# circuitMain.net
KiCad netlist of a schematic drawn in Altium Designer
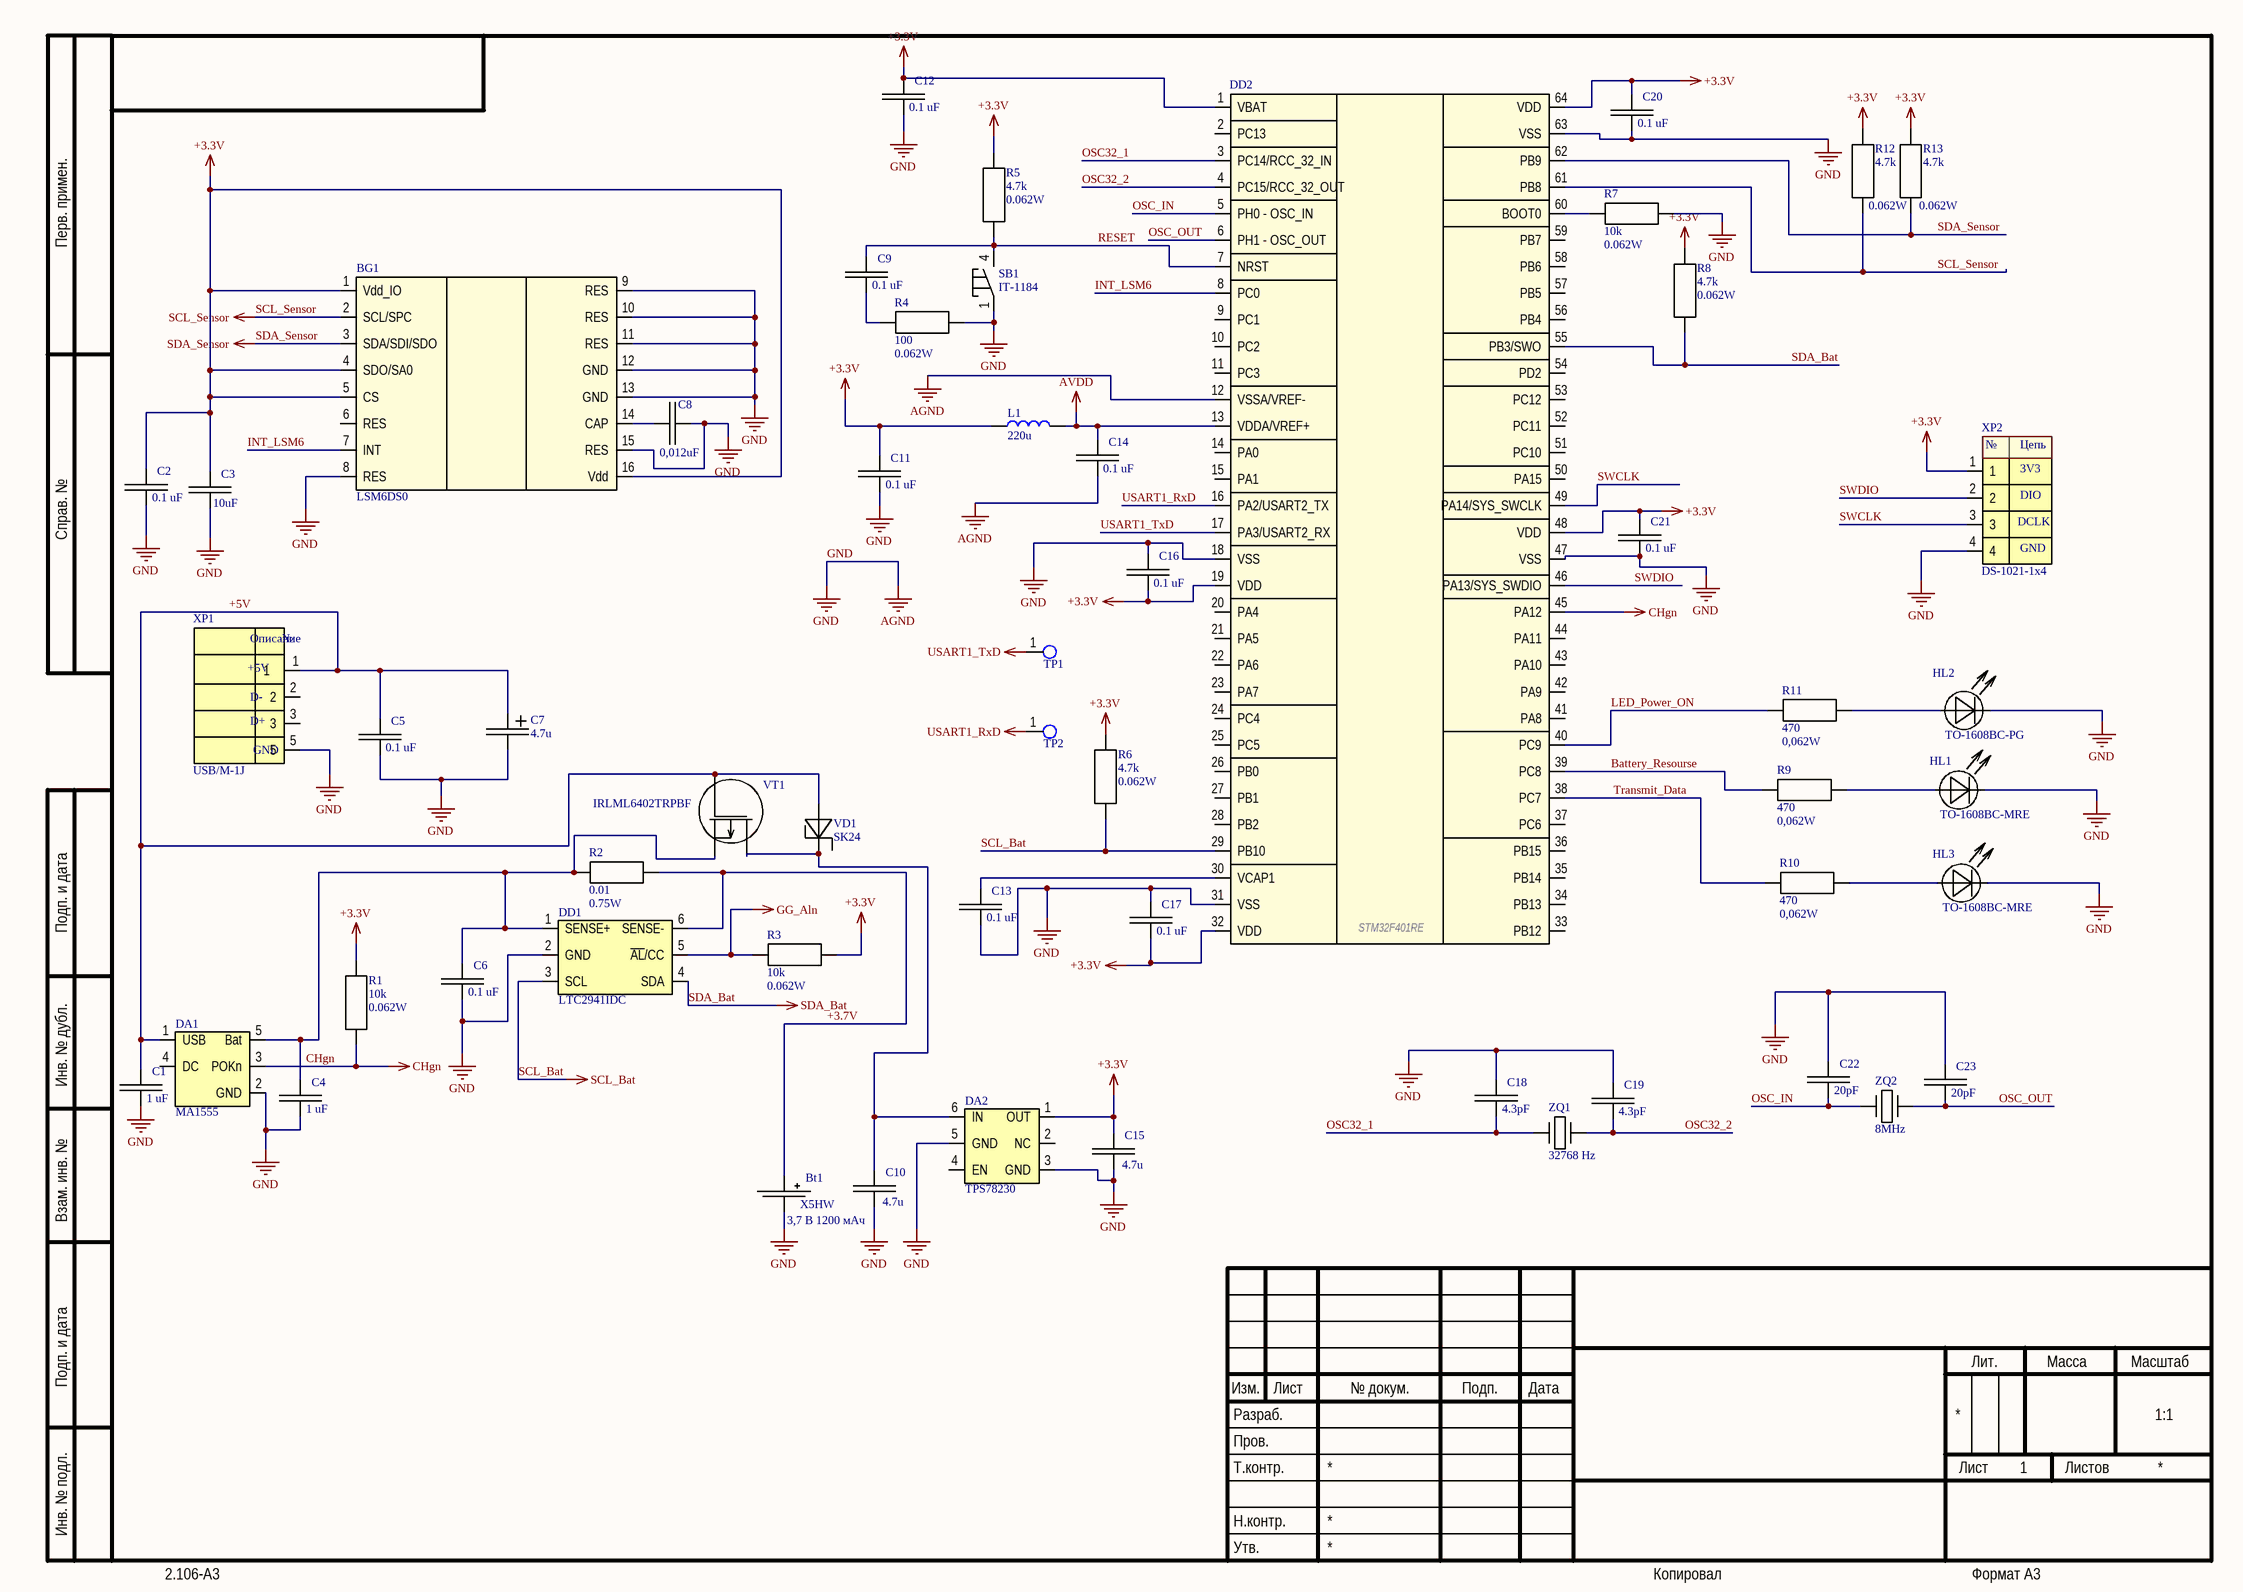
[diagram p0: circuitMain.SchDoc]

(export (version "E")
  (design (tool "Eeschema 10.0.6"))
  (components
    (comp (ref "BG1")
      (value "LSM6DS0")
      (footprint "LGA-16")
      (description "IMEMO")
      (libsource (lib "SchlibUGO") (part "LSM6DS0"))
    )
    (comp (ref "Bt1")
      (value "X5HW")
      (footprint "X5HW")
      (fields
        (field (name "ALTIUM_VALUE") "3,7 В 1200 мАч")
        (field (name "PART NUMBER") "2025")
        (field (name "MANUFACTURER") "china")
      )
      (libsource (lib "SchlibUGO") (part "X5HW"))
    )
    (comp (ref "C1")
      (value "1 uF")
      (footprint "CAP0402_min")
      (fields
        (field (name "VOLTAGE") "10V")
        (field (name "PART NUMBER") "GRM155R61A105KE15B")
        (field (name "MANUFACTURER") "Murata Manufacturing")
      )
      (libsource (lib "") (part "Capasitor_1"))
    )
    (comp (ref "C2")
      (value "0.1 uF")
      (footprint "CAP0402_min")
      (fields
        (field (name "VOLTAGE") "50V")
        (field (name "PART NUMBER") "C1005X7R1H104KT000F")
        (field (name "MANUFACTURER") "TDK")
      )
      (libsource (lib "") (part "Capasitor_1"))
    )
    (comp (ref "C3")
      (value "10uF")
      (footprint "CAP0402_min")
      (fields
        (field (name "VOLTAGE") "50V")
        (field (name "PART NUMBER") "GRM1535C1H100J")
        (field (name "MANUFACTURER") "Murata Manufacturing")
      )
      (libsource (lib "") (part "Capasitor_1"))
    )
    (comp (ref "C4")
      (value "1 uF")
      (footprint "CAP0402_min")
      (fields
        (field (name "VOLTAGE") "10V")
        (field (name "PART NUMBER") "GRM155R61A105KE15B")
        (field (name "MANUFACTURER") "Murata Manufacturing")
      )
      (libsource (lib "") (part "Capasitor_1"))
    )
    (comp (ref "C5")
      (value "0.1 uF")
      (footprint "CAP0402_min")
      (fields
        (field (name "VOLTAGE") "50V")
        (field (name "PART NUMBER") "C1005X7R1H104KT000F")
        (field (name "MANUFACTURER") "TDK")
      )
      (libsource (lib "") (part "Capasitor_1"))
    )
    (comp (ref "C6")
      (value "0.1 uF")
      (footprint "CAP0402_min")
      (fields
        (field (name "VOLTAGE") "50V")
        (field (name "PART NUMBER") "C1005X7R1H104KT000F")
        (field (name "MANUFACTURER") "TDK")
      )
      (libsource (lib "") (part "Capasitor_1"))
    )
    (comp (ref "C7")
      (value "4.7u")
      (footprint "Capasitor Tantal TypeA MIN")
      (fields
        (field (name "PART NUMBER") "TECAP4.7/16VA10")
        (field (name "MANUFACTURER") "China")
        (field (name "POWER") "16V")
      )
      (libsource (lib "SchlibUGO") (part "Capasitor Electrolit"))
    )
    (comp (ref "C8")
      (value "0,012uF")
      (footprint "CAP0402_min")
      (fields
        (field (name "VOLTAGE") "50V")
        (field (name "PART NUMBER") "GRM155R71H123K")
        (field (name "MANUFACTURER") "Murata Manufacturing")
      )
      (libsource (lib "") (part "Capasitor_1"))
    )
    (comp (ref "C9")
      (value "0.1 uF")
      (footprint "CAP0402_min")
      (fields
        (field (name "VOLTAGE") "50V")
        (field (name "PART NUMBER") "C1005X7R1H104KT000F")
        (field (name "MANUFACTURER") "TDK")
      )
      (libsource (lib "SchlibUGO") (part "Capasitor"))
    )
    (comp (ref "C10")
      (value "4.7u")
      (footprint "CAP0402_min")
      (fields
        (field (name "VOLTAGE") "50V")
        (field (name "PART NUMBER") "GRM2165C1H4R7CD01D")
        (field (name "MANUFACTURER") "Murata Manufacturing")
      )
      (libsource (lib "") (part "Capasitor_1"))
    )
    (comp (ref "C11")
      (value "0.1 uF")
      (footprint "CAP0402_min")
      (fields
        (field (name "VOLTAGE") "50V")
        (field (name "PART NUMBER") "C1005X7R1H104KT000F")
        (field (name "MANUFACTURER") "TDK")
      )
      (libsource (lib "") (part "Capasitor_1"))
    )
    (comp (ref "C12")
      (value "0.1 uF")
      (footprint "CAP0402_min")
      (fields
        (field (name "VOLTAGE") "50V")
        (field (name "PART NUMBER") "C1005X7R1H104KT000F")
        (field (name "MANUFACTURER") "TDK")
      )
      (libsource (lib "") (part "Capasitor_1"))
    )
    (comp (ref "C13")
      (value "0.1 uF")
      (footprint "CAP0402_min")
      (fields
        (field (name "VOLTAGE") "50V")
        (field (name "PART NUMBER") "C1005X7R1H104KT000F")
        (field (name "MANUFACTURER") "TDK")
      )
      (libsource (lib "") (part "Capasitor_1"))
    )
    (comp (ref "C14")
      (value "0.1 uF")
      (footprint "CAP0402_min")
      (fields
        (field (name "VOLTAGE") "50V")
        (field (name "PART NUMBER") "C1005X7R1H104KT000F")
        (field (name "MANUFACTURER") "TDK")
      )
      (libsource (lib "") (part "Capasitor_1"))
    )
    (comp (ref "C15")
      (value "4.7u")
      (footprint "CAP0402_min")
      (fields
        (field (name "VOLTAGE") "50V")
        (field (name "PART NUMBER") "GRM2165C1H4R7CD01D")
        (field (name "MANUFACTURER") "Murata Manufacturing")
      )
      (libsource (lib "") (part "Capasitor_1"))
    )
    (comp (ref "C16")
      (value "0.1 uF")
      (footprint "CAP0402_min")
      (fields
        (field (name "VOLTAGE") "50V")
        (field (name "PART NUMBER") "C1005X7R1H104KT000F")
        (field (name "MANUFACTURER") "TDK")
      )
      (libsource (lib "") (part "Capasitor_1"))
    )
    (comp (ref "C17")
      (value "0.1 uF")
      (footprint "CAP0402_min")
      (fields
        (field (name "VOLTAGE") "50V")
        (field (name "PART NUMBER") "C1005X7R1H104KT000F")
        (field (name "MANUFACTURER") "TDK")
      )
      (libsource (lib "") (part "Capasitor_1"))
    )
    (comp (ref "C18")
      (value "4.3pF")
      (footprint "CAP0402_min")
      (fields
        (field (name "VOLTAGE") "50V")
        (field (name "PART NUMBER") "CL05C4R7BB5NNNC")
        (field (name "MANUFACTURER") "Samsung")
      )
      (libsource (lib "") (part "Capasitor_1"))
    )
    (comp (ref "C19")
      (value "4.3pF")
      (footprint "CAP0402_min")
      (fields
        (field (name "VOLTAGE") "50V")
        (field (name "PART NUMBER") "CL05C4R7BB5NNNC")
        (field (name "MANUFACTURER") "Samsung")
      )
      (libsource (lib "") (part "Capasitor_1"))
    )
    (comp (ref "C20")
      (value "0.1 uF")
      (footprint "CAP0402_min")
      (fields
        (field (name "VOLTAGE") "50V")
        (field (name "PART NUMBER") "C1005X7R1H104KT000F")
        (field (name "MANUFACTURER") "TDK")
      )
      (libsource (lib "") (part "Capasitor_1"))
    )
    (comp (ref "C21")
      (value "0.1 uF")
      (footprint "CAP0402_min")
      (fields
        (field (name "VOLTAGE") "50V")
        (field (name "PART NUMBER") "C1005X7R1H104KT000F")
        (field (name "MANUFACTURER") "TDK")
      )
      (libsource (lib "") (part "Capasitor_1"))
    )
    (comp (ref "C22")
      (value "20pF")
      (footprint "CAP0402_min")
      (fields
        (field (name "VOLTAGE") "50V")
        (field (name "PART NUMBER") "CL05C220JB5NNNC")
        (field (name "MANUFACTURER") "Samsung")
      )
      (libsource (lib "") (part "Capasitor_1"))
    )
    (comp (ref "C23")
      (value "20pF")
      (footprint "CAP0402_min")
      (fields
        (field (name "VOLTAGE") "50V")
        (field (name "PART NUMBER") "CL05C220JB5NNNC")
        (field (name "MANUFACTURER") "Samsung")
      )
      (libsource (lib "") (part "Capasitor_1"))
    )
    (comp (ref "DA1")
      (value "MA1555")
      (footprint "SOT23-5")
      (fields
        (field (name "PART NUMBER") "MAX1555EZK+T")
        (field (name "MANUFACTURER") "Maxim Integrated Products")
      )
      (libsource (lib "SchlibUGO") (part "MAX1555"))
    )
    (comp (ref "DA2")
      (value "TPS78230")
      (footprint "WSON-6")
      (fields (field (name "PART NUMBER") "TSOT23-5") (field (name "MANUFACTURER") "Texas Instruments"))
      (libsource (lib "SchlibUGO") (part "TPS78230"))
    )
    (comp (ref "DD1")
      (value "LTC2941IDC")
      (footprint "DFN-6")
      (fields (field (name "MANUFACTURER") "RoHS Compliant"))
      (libsource (lib "SchlibUGO") (part "LTC2941IDC"))
    )
    (comp (ref "DD2")
      (value "STM32F401RE")
      (footprint "LQFP-64")
      (fields (field (name "MANUFACTURER") "STM MicroElectronics") (field (name "PART NUMBER") "STM32F401RE"))
      (libsource (lib "Integrated_MicroprocessorLib") (part "STM32F401RE"))
    )
    (comp (ref "HL1")
      (value "TO-1608BC-MRE")
      (footprint "LED1206")
      (fields (field (name "MANUFACTURER") "Taiwan Oasis Technology Co"))
      (libsource (lib "SchlibUGO") (part "LED"))
    )
    (comp (ref "HL2")
      (value "TO-1608BC-PG")
      (footprint "LED1206")
      (fields (field (name "MANUFACTURER") "Taiwan Oasis Technology"))
      (libsource (lib "SchlibUGO") (part "LED"))
    )
    (comp (ref "HL3")
      (value "TO-1608BC-MRE")
      (footprint "LED1206")
      (fields (field (name "MANUFACTURER") "Taiwan Oasis Technology Co"))
      (libsource (lib "SchlibUGO") (part "LED"))
    )
    (comp (ref "L1")
      (value "220u")
      (footprint "LQG15HN15NJ")
      (fields (field (name "PART NUMBER") "CM453232-221KL") (field (name "MANUFACTURER") "Bourns"))
      (libsource (lib "SchlibUGO") (part "Inductor"))
    )
    (comp (ref "R1")
      (value "10k")
      (footprint "0402")
      (fields
        (field (name "MANUFACTURER") "Тайвань")
        (field (name "PART NUMBER") "RC0402FR-0710KL")
        (field (name "POWER") "0.062W")
      )
      (libsource (lib "SchlibUGO") (part "Resistor"))
    )
    (comp (ref "R2")
      (value "0.01")
      (footprint "1206")
      (fields
        (field (name "MANUFACTURER") "China")
        (field (name "PART NUMBER") "120600R1")
        (field (name "POWER") "0.75W")
      )
      (libsource (lib "SchlibUGO") (part "Resistor"))
    )
    (comp (ref "R3")
      (value "10k")
      (footprint "0402")
      (fields
        (field (name "MANUFACTURER") "Тайвань")
        (field (name "PART NUMBER") "RC0402FR-0710KL")
        (field (name "POWER") "0.062W")
      )
      (libsource (lib "SchlibUGO") (part "Resistor"))
    )
    (comp (ref "R4")
      (value "100")
      (footprint "0402")
      (fields
        (field (name "MANUFACTURER") "Тайвань")
        (field (name "PART NUMBER") "RC0603FR-07100RL")
        (field (name "POWER") "0.062W")
      )
      (libsource (lib "SchlibUGO") (part "Resistor"))
    )
    (comp (ref "R5")
      (value "4.7k")
      (footprint "0402")
      (fields
        (field (name "MANUFACTURER") "Тайвань")
        (field (name "PART NUMBER") "RC0402JR-074K7L")
        (field (name "POWER") "0.062W")
      )
      (libsource (lib "SchlibUGO") (part "Resistor"))
    )
    (comp (ref "R6")
      (value "4.7k")
      (footprint "0402")
      (fields
        (field (name "MANUFACTURER") "Тайвань")
        (field (name "PART NUMBER") "RC0402JR-074K7L")
        (field (name "POWER") "0.062W")
      )
      (libsource (lib "SchlibUGO") (part "Resistor"))
    )
    (comp (ref "R7")
      (value "10k")
      (footprint "0402")
      (fields
        (field (name "MANUFACTURER") "Тайвань")
        (field (name "PART NUMBER") "RC0402FR-0710KL")
        (field (name "POWER") "0.062W")
      )
      (libsource (lib "SchlibUGO") (part "Resistor"))
    )
    (comp (ref "R8")
      (value "4.7k")
      (footprint "0402")
      (fields
        (field (name "MANUFACTURER") "Тайвань")
        (field (name "PART NUMBER") "RC0402JR-074K7L")
        (field (name "POWER") "0.062W")
      )
      (libsource (lib "") (part "Resistor_1"))
    )
    (comp (ref "R9")
      (value "470")
      (footprint "0402")
      (fields
        (field (name "MANUFACTURER") "Тайвань")
        (field (name "PART NUMBER") "RC0805FR-07470RL")
        (field (name "POWER") "0,062W")
      )
      (libsource (lib "SchlibUGO") (part "Resistor"))
    )
    (comp (ref "R10")
      (value "470")
      (footprint "0402")
      (fields
        (field (name "MANUFACTURER") "Тайвань")
        (field (name "PART NUMBER") "RC0805FR-07470RL")
        (field (name "POWER") "0,062W")
      )
      (libsource (lib "SchlibUGO") (part "Resistor"))
    )
    (comp (ref "R11")
      (value "470")
      (footprint "0402")
      (fields
        (field (name "MANUFACTURER") "Тайвань")
        (field (name "PART NUMBER") "RC0805FR-07470RL")
        (field (name "POWER") "0,062W")
      )
      (libsource (lib "SchlibUGO") (part "Resistor"))
    )
    (comp (ref "R12")
      (value "4.7k")
      (footprint "0402")
      (fields
        (field (name "MANUFACTURER") "Тайвань")
        (field (name "PART NUMBER") "RC0402JR-074K7L")
        (field (name "POWER") "0.062W")
      )
      (libsource (lib "SchlibUGO") (part "Resistor"))
    )
    (comp (ref "R13")
      (value "4.7k")
      (footprint "0402")
      (fields
        (field (name "MANUFACTURER") "Тайвань")
        (field (name "PART NUMBER") "RC0402JR-074K7L")
        (field (name "POWER") "0.062W")
      )
      (libsource (lib "SchlibUGO") (part "Resistor"))
    )
    (comp (ref "SB1")
      (value "IT-1184")
      (footprint "IT-1184")
      (fields (field (name "MANUFACTURER") "China"))
      (libsource (lib "SchlibUGO") (part "Button"))
    )
    (comp (ref "TP1") (value "TP") (footprint "TP_Hole") (libsource (lib "SchlibUGO") (part "TP")))
    (comp (ref "TP2") (value "TP") (footprint "TP_Hole") (libsource (lib "SchlibUGO") (part "TP")))
    (comp (ref "VD1")
      (value "SK24")
      (footprint "DO-214(SMB)")
      (fields (field (name "POWER") "80W"))
      (libsource (lib "Diode_Library") (part "Basic_Diode_shottki"))
    )
    (comp (ref "VT1")
      (value "IRLML6402TRPBF")
      (footprint "SOT23-3")
      (fields (field (name "MANUFACTURER") "International rectifier"))
      (libsource (lib "Project_int_VT") (part "IRLML6402"))
    )
    (comp (ref "XP1")
      (value "USB/M-1J")
      (footprint "USB/M-1J")
      (fields (field (name "MANUFACTURER") "ESB"))
      (libsource (lib "SchlibUGO") (part "USB-M-1J"))
    )
    (comp (ref "XP2")
      (value "DS-1021-1x4")
      (footprint "Connector_STKLink")
      (fields (field (name "MANUFACTURER") "Ningbo connfly electronic"))
      (libsource (lib "SchlibUGO") (part "Connector_STKLink"))
    )
    (comp (ref "ZQ1")
      (value "32768 Hz")
      (footprint "KX-26")
      (fields (field (name "PART NUMBER") "KX-26") (field (name "MANUFACTURER") "CHina"))
      (libsource (lib "SchlibUGO") (part "Rzanator"))
    )
    (comp (ref "ZQ2")
      (value "8MHz")
      (footprint "SMD0503")
      (fields (field (name "PART NUMBER") "SMD0503(4P)") (field (name "MANUFACTURER") "CHina"))
      (libsource (lib "SchlibUGO") (part "Rzanator"))
    )
  )
  (nets
    (net (code "1") (name "+3.3V") (class "Default")
      (node (ref "BG1") (pin "1") (pinfunction "Vdd_IO_1") (pintype "passive"))
      (node (ref "BG1") (pin "16") (pinfunction "Vdd_16") (pintype "passive"))
      (node (ref "BG1") (pin "4") (pinfunction "SDO/SA0_4") (pintype "passive"))
      (node (ref "BG1") (pin "5") (pinfunction "CS_5") (pintype "passive"))
      (node (ref "C11") (pin "1") (pinfunction "1_1") (pintype "passive"))
      (node (ref "C12") (pin "1") (pinfunction "1_1") (pintype "passive"))
      (node (ref "C15") (pin "1") (pinfunction "1_1") (pintype "passive"))
      (node (ref "C16") (pin "2") (pinfunction "2_2") (pintype "passive"))
      (node (ref "C17") (pin "2") (pinfunction "2_2") (pintype "passive"))
      (node (ref "C2") (pin "1") (pinfunction "1_1") (pintype "passive"))
      (node (ref "C20") (pin "1") (pinfunction "1_1") (pintype "passive"))
      (node (ref "C21") (pin "1") (pinfunction "1_1") (pintype "passive"))
      (node (ref "C3") (pin "1") (pinfunction "1_1") (pintype "passive"))
      (node (ref "DA2") (pin "1") (pinfunction "OUT_1") (pintype "passive"))
      (node (ref "DD2") (pin "1") (pinfunction "VBAT_1") (pintype "passive"))
      (node (ref "DD2") (pin "19") (pinfunction "VDD_19") (pintype "passive"))
      (node (ref "DD2") (pin "32") (pinfunction "VDD_32") (pintype "passive"))
      (node (ref "DD2") (pin "48") (pinfunction "VDD_48") (pintype "passive"))
      (node (ref "DD2") (pin "64") (pinfunction "VDD_64") (pintype "passive"))
      (node (ref "L1") (pin "1") (pinfunction "1_1") (pintype "passive"))
      (node (ref "R1") (pin "2") (pinfunction "2_2") (pintype "passive"))
      (node (ref "R12") (pin "2") (pinfunction "2_2") (pintype "passive"))
      (node (ref "R13") (pin "2") (pinfunction "2_2") (pintype "passive"))
      (node (ref "R3") (pin "1") (pinfunction "1_1") (pintype "passive"))
      (node (ref "R5") (pin "2") (pinfunction "2_2") (pintype "passive"))
      (node (ref "R6") (pin "2") (pinfunction "2_2") (pintype "passive"))
      (node (ref "R8") (pin "2") (pinfunction "2_2") (pintype "passive"))
      (node (ref "XP2") (pin "1") (pinfunction "1_1") (pintype "passive"))
    )
    (net (code "2") (name "/+3.7V") (class "Default")
      (node (ref "Bt1") (pin "1") (pinfunction "1_1") (pintype "passive"))
      (node (ref "DD1") (pin "6") (pinfunction "SENSE-_6") (pintype "passive"))
      (node (ref "R2") (pin "2") (pinfunction "2_2") (pintype "passive"))
    )
    (net (code "3") (name "/+5V") (class "Default")
      (node (ref "C1") (pin "1") (pinfunction "1_1") (pintype "passive"))
      (node (ref "C5") (pin "1") (pinfunction "1_1") (pintype "passive"))
      (node (ref "C7") (pin "1") (pinfunction "1_1") (pintype "passive"))
      (node (ref "DA1") (pin "1") (pinfunction "USB_1") (pintype "passive"))
      (node (ref "VD1") (pin "1") (pinfunction "1_1") (pintype "passive"))
      (node (ref "VT1") (pin "1") (pinfunction "G_1") (pintype "passive"))
      (node (ref "XP1") (pin "1") (pinfunction "1_1") (pintype "passive"))
    )
    (net (code "4") (name "/Battery_Resourse") (class "Default")
      (node (ref "DD2") (pin "39") (pinfunction "PC8_39") (pintype "passive"))
      (node (ref "R9") (pin "2") (pinfunction "2_2") (pintype "passive"))
    )
    (net (code "5") (name "/INT_LSM6") (class "Default")
      (node (ref "BG1") (pin "7") (pinfunction "INT_7") (pintype "passive"))
      (node (ref "DD2") (pin "8") (pinfunction "PC0_8") (pintype "passive"))
    )
    (net (code "6") (name "/LED_Power_ON") (class "Default")
      (node (ref "DD2") (pin "40") (pinfunction "PC9_40") (pintype "passive"))
      (node (ref "R11") (pin "2") (pinfunction "2_2") (pintype "passive"))
    )
    (net (code "7") (name "/OSC32_1") (class "Default")
      (node (ref "C18") (pin "2") (pinfunction "2_2") (pintype "passive"))
      (node (ref "DD2") (pin "3") (pinfunction "PC14/RCC_32_IN_3") (pintype "passive"))
      (node (ref "ZQ1") (pin "1") (pinfunction "1_1") (pintype "passive"))
    )
    (net (code "8") (name "/OSC32_2") (class "Default")
      (node (ref "C19") (pin "2") (pinfunction "2_2") (pintype "passive"))
      (node (ref "DD2") (pin "4") (pinfunction "PC15/RCC_32_OUT_4") (pintype "passive"))
      (node (ref "ZQ1") (pin "3") (pinfunction "2_3") (pintype "passive"))
    )
    (net (code "9") (name "/OSC_IN") (class "Default")
      (node (ref "C22") (pin "2") (pinfunction "2_2") (pintype "passive"))
      (node (ref "DD2") (pin "5") (pinfunction "PH0_-_OSC_IN_5") (pintype "passive"))
      (node (ref "ZQ2") (pin "1") (pinfunction "1_1") (pintype "passive"))
    )
    (net (code "10") (name "/OSC_OUT") (class "Default")
      (node (ref "C23") (pin "2") (pinfunction "2_2") (pintype "passive"))
      (node (ref "DD2") (pin "6") (pinfunction "PH1_-_OSC_OUT_6") (pintype "passive"))
      (node (ref "ZQ2") (pin "3") (pinfunction "2_3") (pintype "passive"))
    )
    (net (code "11") (name "/RESET") (class "Default")
      (node (ref "C9") (pin "1") (pinfunction "1_1") (pintype "passive"))
      (node (ref "DD2") (pin "7") (pinfunction "NRST_7") (pintype "passive"))
      (node (ref "R5") (pin "1") (pinfunction "1_1") (pintype "passive"))
      (node (ref "SB1") (pin "4") (pinfunction "4_4") (pintype "passive"))
    )
    (net (code "12") (name "/SWCLK") (class "Default")
      (node (ref "DD2") (pin "49") (pinfunction "PA14/SYS_SWCLK_49") (pintype "passive"))
      (node (ref "XP2") (pin "3") (pinfunction "3_3") (pintype "passive"))
    )
    (net (code "13") (name "/SWDIO") (class "Default")
      (node (ref "DD2") (pin "46") (pinfunction "PA13/SYS_SWDIO_46") (pintype "passive"))
      (node (ref "XP2") (pin "2") (pinfunction "2_2") (pintype "passive"))
    )
    (net (code "14") (name "/Transmit_Data") (class "Default")
      (node (ref "DD2") (pin "38") (pinfunction "PC7_38") (pintype "passive"))
      (node (ref "R10") (pin "2") (pinfunction "2_2") (pintype "passive"))
    )
    (net (code "15") (name "AGND") (class "Default")
      (node (ref "BG1") (pin "10") (pinfunction "RES_10") (pintype "passive"))
      (node (ref "BG1") (pin "11") (pinfunction "RES_11") (pintype "passive"))
      (node (ref "BG1") (pin "12") (pinfunction "GND_12") (pintype "passive"))
      (node (ref "BG1") (pin "13") (pinfunction "GND_13") (pintype "passive"))
      (node (ref "BG1") (pin "15") (pinfunction "RES_15") (pintype "passive"))
      (node (ref "BG1") (pin "8") (pinfunction "RES_8") (pintype "passive"))
      (node (ref "BG1") (pin "9") (pinfunction "RES_9") (pintype "passive"))
      (node (ref "Bt1") (pin "2") (pinfunction "2_2") (pintype "passive"))
      (node (ref "C1") (pin "2") (pinfunction "2_2") (pintype "passive"))
      (node (ref "C10") (pin "2") (pinfunction "2_2") (pintype "passive"))
      (node (ref "C11") (pin "2") (pinfunction "2_2") (pintype "passive"))
      (node (ref "C12") (pin "2") (pinfunction "2_2") (pintype "passive"))
      (node (ref "C13") (pin "2") (pinfunction "2_2") (pintype "passive"))
      (node (ref "C14") (pin "2") (pinfunction "2_2") (pintype "passive"))
      (node (ref "C15") (pin "2") (pinfunction "2_2") (pintype "passive"))
      (node (ref "C16") (pin "1") (pinfunction "1_1") (pintype "passive"))
      (node (ref "C17") (pin "1") (pinfunction "1_1") (pintype "passive"))
      (node (ref "C18") (pin "1") (pinfunction "1_1") (pintype "passive"))
      (node (ref "C19") (pin "1") (pinfunction "1_1") (pintype "passive"))
      (node (ref "C2") (pin "2") (pinfunction "2_2") (pintype "passive"))
      (node (ref "C20") (pin "2") (pinfunction "2_2") (pintype "passive"))
      (node (ref "C21") (pin "2") (pinfunction "2_2") (pintype "passive"))
      (node (ref "C22") (pin "1") (pinfunction "1_1") (pintype "passive"))
      (node (ref "C23") (pin "1") (pinfunction "1_1") (pintype "passive"))
      (node (ref "C3") (pin "2") (pinfunction "2_2") (pintype "passive"))
      (node (ref "C4") (pin "2") (pinfunction "2_2") (pintype "passive"))
      (node (ref "C5") (pin "2") (pinfunction "2_2") (pintype "passive"))
      (node (ref "C6") (pin "2") (pinfunction "2_2") (pintype "passive"))
      (node (ref "C7") (pin "2") (pinfunction "2_2") (pintype "passive"))
      (node (ref "C8") (pin "2") (pinfunction "2_2") (pintype "passive"))
      (node (ref "DA1") (pin "2") (pinfunction "GND_2") (pintype "passive"))
      (node (ref "DA2") (pin "3") (pinfunction "GND_3") (pintype "passive"))
      (node (ref "DA2") (pin "5") (pinfunction "GND_5") (pintype "passive"))
      (node (ref "DD1") (pin "2") (pinfunction "GND_2") (pintype "passive"))
      (node (ref "DD2") (pin "12") (pinfunction "VSSA/VREF-_12") (pintype "passive"))
      (node (ref "DD2") (pin "18") (pinfunction "VSS_18") (pintype "passive"))
      (node (ref "DD2") (pin "31") (pinfunction "VSS_31") (pintype "passive"))
      (node (ref "DD2") (pin "47") (pinfunction "VSS_47") (pintype "passive"))
      (node (ref "DD2") (pin "63") (pinfunction "VSS_63") (pintype "passive"))
      (node (ref "HL1") (pin "2") (pinfunction "2_2") (pintype "passive"))
      (node (ref "HL2") (pin "2") (pinfunction "2_2") (pintype "passive"))
      (node (ref "HL3") (pin "2") (pinfunction "2_2") (pintype "passive"))
      (node (ref "R4") (pin "1") (pinfunction "1_1") (pintype "passive"))
      (node (ref "R7") (pin "1") (pinfunction "1_1") (pintype "passive"))
      (node (ref "SB1") (pin "1") (pinfunction "1_1") (pintype "passive"))
      (node (ref "XP1") (pin "5") (pinfunction "5_5") (pintype "passive"))
      (node (ref "XP2") (pin "4") (pinfunction "4_4") (pintype "passive"))
    )
    (net (code "16") (name "AVDD") (class "Default")
      (node (ref "C14") (pin "1") (pinfunction "1_1") (pintype "passive"))
      (node (ref "DD2") (pin "13") (pinfunction "VDDA/VREF+_13") (pintype "passive"))
      (node (ref "L1") (pin "2") (pinfunction "2_2") (pintype "passive"))
    )
    (net (code "17") (name "CHgn") (class "Default")
      (node (ref "DA1") (pin "3") (pinfunction "POKn_3") (pintype "passive"))
      (node (ref "DD2") (pin "45") (pinfunction "PA12_45") (pintype "passive"))
      (node (ref "R1") (pin "1") (pinfunction "1_1") (pintype "passive"))
    )
    (net (code "18") (name "GG_Aln") (class "Default")
      (node (ref "DD1") (pin "5") (pinfunction "~{AL}/CC_5") (pintype "passive"))
      (node (ref "R3") (pin "2") (pinfunction "2_2") (pintype "passive"))
    )
    (net (code "19") (name "Net-(BG1-CAP)") (class "Default")
      (node (ref "BG1") (pin "14") (pinfunction "CAP_14") (pintype "passive"))
      (node (ref "C8") (pin "1") (pinfunction "1_1") (pintype "passive"))
    )
    (net (code "20") (name "Net-(C9-Pad2)") (class "Default")
      (node (ref "C9") (pin "2") (pinfunction "2_2") (pintype "passive"))
      (node (ref "R4") (pin "2") (pinfunction "2_2") (pintype "passive"))
    )
    (net (code "21") (name "Net-(DA1-Bat)") (class "Default")
      (node (ref "C4") (pin "1") (pinfunction "1_1") (pintype "passive"))
      (node (ref "C6") (pin "1") (pinfunction "1_1") (pintype "passive"))
      (node (ref "DA1") (pin "5") (pinfunction "Bat_5") (pintype "passive"))
      (node (ref "DD1") (pin "1") (pinfunction "SENSE+_1") (pintype "passive"))
      (node (ref "R2") (pin "1") (pinfunction "1_1") (pintype "passive"))
      (node (ref "VT1") (pin "2") (pinfunction "Source_2") (pintype "passive"))
    )
    (net (code "22") (name "Net-(DA2-IN)") (class "Default")
      (node (ref "C10") (pin "1") (pinfunction "1_1") (pintype "passive"))
      (node (ref "DA2") (pin "6") (pinfunction "IN_6") (pintype "passive"))
      (node (ref "VD1") (pin "2") (pinfunction "2_2") (pintype "passive"))
      (node (ref "VT1") (pin "3") (pinfunction "D_3") (pintype "passive"))
    )
    (net (code "23") (name "Net-(DD2-BOOT0)") (class "Default")
      (node (ref "DD2") (pin "60") (pinfunction "BOOT0_60") (pintype "passive"))
      (node (ref "R7") (pin "2") (pinfunction "2_2") (pintype "passive"))
    )
    (net (code "24") (name "Net-(DD2-VCAP1)") (class "Default")
      (node (ref "C13") (pin "1") (pinfunction "1_1") (pintype "passive"))
      (node (ref "DD2") (pin "30") (pinfunction "VCAP1_30") (pintype "passive"))
    )
    (net (code "25") (name "Net-(HL1-Pad1)") (class "Default")
      (node (ref "HL1") (pin "1") (pinfunction "1_1") (pintype "passive"))
      (node (ref "R9") (pin "1") (pinfunction "1_1") (pintype "passive"))
    )
    (net (code "26") (name "Net-(HL2-Pad1)") (class "Default")
      (node (ref "HL2") (pin "1") (pinfunction "1_1") (pintype "passive"))
      (node (ref "R11") (pin "1") (pinfunction "1_1") (pintype "passive"))
    )
    (net (code "27") (name "Net-(HL3-Pad1)") (class "Default")
      (node (ref "HL3") (pin "1") (pinfunction "1_1") (pintype "passive"))
      (node (ref "R10") (pin "1") (pinfunction "1_1") (pintype "passive"))
    )
    (net (code "28") (name "SCL_Bat") (class "Default")
      (node (ref "DD1") (pin "3") (pinfunction "SCL_3") (pintype "passive"))
      (node (ref "DD2") (pin "29") (pinfunction "PB10_29") (pintype "passive"))
      (node (ref "R6") (pin "1") (pinfunction "1_1") (pintype "passive"))
    )
    (net (code "29") (name "SCL_Sensor") (class "Default")
      (node (ref "BG1") (pin "2") (pinfunction "SCL/SPC_2") (pintype "passive"))
      (node (ref "DD2") (pin "61") (pinfunction "PB8_61") (pintype "passive"))
      (node (ref "R12") (pin "1") (pinfunction "1_1") (pintype "passive"))
    )
    (net (code "30") (name "SDA_Bat") (class "Default")
      (node (ref "DD1") (pin "4") (pinfunction "SDA_4") (pintype "passive"))
      (node (ref "DD2") (pin "55") (pinfunction "PB3/SWO_55") (pintype "passive"))
      (node (ref "R8") (pin "1") (pinfunction "1_1") (pintype "passive"))
    )
    (net (code "31") (name "SDA_Sensor") (class "Default")
      (node (ref "BG1") (pin "3") (pinfunction "SDA/SDI/SDO_3") (pintype "passive"))
      (node (ref "DD2") (pin "62") (pinfunction "PB9_62") (pintype "passive"))
      (node (ref "R13") (pin "1") (pinfunction "1_1") (pintype "passive"))
    )
    (net (code "32") (name "USART1_RxD") (class "Default")
      (node (ref "DD2") (pin "16") (pinfunction "PA2/USART2_TX_16") (pintype "passive"))
      (node (ref "TP2") (pin "1") (pinfunction "1_1") (pintype "passive"))
    )
    (net (code "33") (name "USART1_TxD") (class "Default")
      (node (ref "DD2") (pin "17") (pinfunction "PA3/USART2_RX_17") (pintype "passive"))
      (node (ref "TP1") (pin "1") (pinfunction "1_1") (pintype "passive"))
    )
    (net (code "34") (name "unconnected-(BG1-RES-Pad6)") (class "Default")
      (node (ref "BG1") (pin "6") (pinfunction "RES_6") (pintype "passive"))
    )
    (net (code "35") (name "unconnected-(DA1-DC-Pad4)") (class "Default")
      (node (ref "DA1") (pin "4") (pinfunction "DC_4") (pintype "passive"))
    )
    (net (code "36") (name "unconnected-(DA2-EN-Pad4)") (class "Default")
      (node (ref "DA2") (pin "4") (pinfunction "EN_4") (pintype "passive"))
    )
    (net (code "37") (name "unconnected-(DA2-NC-Pad2)") (class "Default")
      (node (ref "DA2") (pin "2") (pinfunction "NC_2") (pintype "passive"))
    )
    (net (code "38") (name "unconnected-(DD2-PA0-Pad14)") (class "Default")
      (node (ref "DD2") (pin "14") (pinfunction "PA0_14") (pintype "passive"))
    )
    (net (code "39") (name "unconnected-(DD2-PA1-Pad15)") (class "Default")
      (node (ref "DD2") (pin "15") (pinfunction "PA1_15") (pintype "passive"))
    )
    (net (code "40") (name "unconnected-(DD2-PA4-Pad20)") (class "Default")
      (node (ref "DD2") (pin "20") (pinfunction "PA4_20") (pintype "passive"))
    )
    (net (code "41") (name "unconnected-(DD2-PA5-Pad21)") (class "Default")
      (node (ref "DD2") (pin "21") (pinfunction "PA5_21") (pintype "passive"))
    )
    (net (code "42") (name "unconnected-(DD2-PA6-Pad22)") (class "Default")
      (node (ref "DD2") (pin "22") (pinfunction "PA6_22") (pintype "passive"))
    )
    (net (code "43") (name "unconnected-(DD2-PA7-Pad23)") (class "Default")
      (node (ref "DD2") (pin "23") (pinfunction "PA7_23") (pintype "passive"))
    )
    (net (code "44") (name "unconnected-(DD2-PA8-Pad41)") (class "Default")
      (node (ref "DD2") (pin "41") (pinfunction "PA8_41") (pintype "passive"))
    )
    (net (code "45") (name "unconnected-(DD2-PA9-Pad42)") (class "Default")
      (node (ref "DD2") (pin "42") (pinfunction "PA9_42") (pintype "passive"))
    )
    (net (code "46") (name "unconnected-(DD2-PA10-Pad43)") (class "Default")
      (node (ref "DD2") (pin "43") (pinfunction "PA10_43") (pintype "passive"))
    )
    (net (code "47") (name "unconnected-(DD2-PA11-Pad44)") (class "Default")
      (node (ref "DD2") (pin "44") (pinfunction "PA11_44") (pintype "passive"))
    )
    (net (code "48") (name "unconnected-(DD2-PA15-Pad50)") (class "Default")
      (node (ref "DD2") (pin "50") (pinfunction "PA15_50") (pintype "passive"))
    )
    (net (code "49") (name "unconnected-(DD2-PB0-Pad26)") (class "Default")
      (node (ref "DD2") (pin "26") (pinfunction "PB0_26") (pintype "passive"))
    )
    (net (code "50") (name "unconnected-(DD2-PB1-Pad27)") (class "Default")
      (node (ref "DD2") (pin "27") (pinfunction "PB1_27") (pintype "passive"))
    )
    (net (code "51") (name "unconnected-(DD2-PB2-Pad28)") (class "Default")
      (node (ref "DD2") (pin "28") (pinfunction "PB2_28") (pintype "passive"))
    )
    (net (code "52") (name "unconnected-(DD2-PB4-Pad56)") (class "Default")
      (node (ref "DD2") (pin "56") (pinfunction "PB4_56") (pintype "passive"))
    )
    (net (code "53") (name "unconnected-(DD2-PB5-Pad57)") (class "Default")
      (node (ref "DD2") (pin "57") (pinfunction "PB5_57") (pintype "passive"))
    )
    (net (code "54") (name "unconnected-(DD2-PB6-Pad58)") (class "Default")
      (node (ref "DD2") (pin "58") (pinfunction "PB6_58") (pintype "passive"))
    )
    (net (code "55") (name "unconnected-(DD2-PB7-Pad59)") (class "Default")
      (node (ref "DD2") (pin "59") (pinfunction "PB7_59") (pintype "passive"))
    )
    (net (code "56") (name "unconnected-(DD2-PB12-Pad33)") (class "Default")
      (node (ref "DD2") (pin "33") (pinfunction "PB12_33") (pintype "passive"))
    )
    (net (code "57") (name "unconnected-(DD2-PB13-Pad34)") (class "Default")
      (node (ref "DD2") (pin "34") (pinfunction "PB13_34") (pintype "passive"))
    )
    (net (code "58") (name "unconnected-(DD2-PB14-Pad35)") (class "Default")
      (node (ref "DD2") (pin "35") (pinfunction "PB14_35") (pintype "passive"))
    )
    (net (code "59") (name "unconnected-(DD2-PB15-Pad36)") (class "Default")
      (node (ref "DD2") (pin "36") (pinfunction "PB15_36") (pintype "passive"))
    )
    (net (code "60") (name "unconnected-(DD2-PC1-Pad9)") (class "Default")
      (node (ref "DD2") (pin "9") (pinfunction "PC1_9") (pintype "passive"))
    )
    (net (code "61") (name "unconnected-(DD2-PC2-Pad10)") (class "Default")
      (node (ref "DD2") (pin "10") (pinfunction "PC2_10") (pintype "passive"))
    )
    (net (code "62") (name "unconnected-(DD2-PC3-Pad11)") (class "Default")
      (node (ref "DD2") (pin "11") (pinfunction "PC3_11") (pintype "passive"))
    )
    (net (code "63") (name "unconnected-(DD2-PC4-Pad24)") (class "Default")
      (node (ref "DD2") (pin "24") (pinfunction "PC4_24") (pintype "passive"))
    )
    (net (code "64") (name "unconnected-(DD2-PC5-Pad25)") (class "Default")
      (node (ref "DD2") (pin "25") (pinfunction "PC5_25") (pintype "passive"))
    )
    (net (code "65") (name "unconnected-(DD2-PC6-Pad37)") (class "Default")
      (node (ref "DD2") (pin "37") (pinfunction "PC6_37") (pintype "passive"))
    )
    (net (code "66") (name "unconnected-(DD2-PC10-Pad51)") (class "Default")
      (node (ref "DD2") (pin "51") (pinfunction "PC10_51") (pintype "passive"))
    )
    (net (code "67") (name "unconnected-(DD2-PC11-Pad52)") (class "Default")
      (node (ref "DD2") (pin "52") (pinfunction "PC11_52") (pintype "passive"))
    )
    (net (code "68") (name "unconnected-(DD2-PC12-Pad53)") (class "Default")
      (node (ref "DD2") (pin "53") (pinfunction "PC12_53") (pintype "passive"))
    )
    (net (code "69") (name "unconnected-(DD2-PC13-Pad2)") (class "Default")
      (node (ref "DD2") (pin "2") (pinfunction "PC13_2") (pintype "passive"))
    )
    (net (code "70") (name "unconnected-(DD2-PD2-Pad54)") (class "Default")
      (node (ref "DD2") (pin "54") (pinfunction "PD2_54") (pintype "passive"))
    )
    (net (code "71") (name "unconnected-(XP1-Pad2)") (class "Default")
      (node (ref "XP1") (pin "2") (pinfunction "2_2") (pintype "passive"))
    )
    (net (code "72") (name "unconnected-(XP1-Pad3)") (class "Default")
      (node (ref "XP1") (pin "3") (pinfunction "3_3") (pintype "passive"))
    )
  )
)
